# BCD_Source.net
KiCad netlist of a schematic drawn in EasyEDA Pro
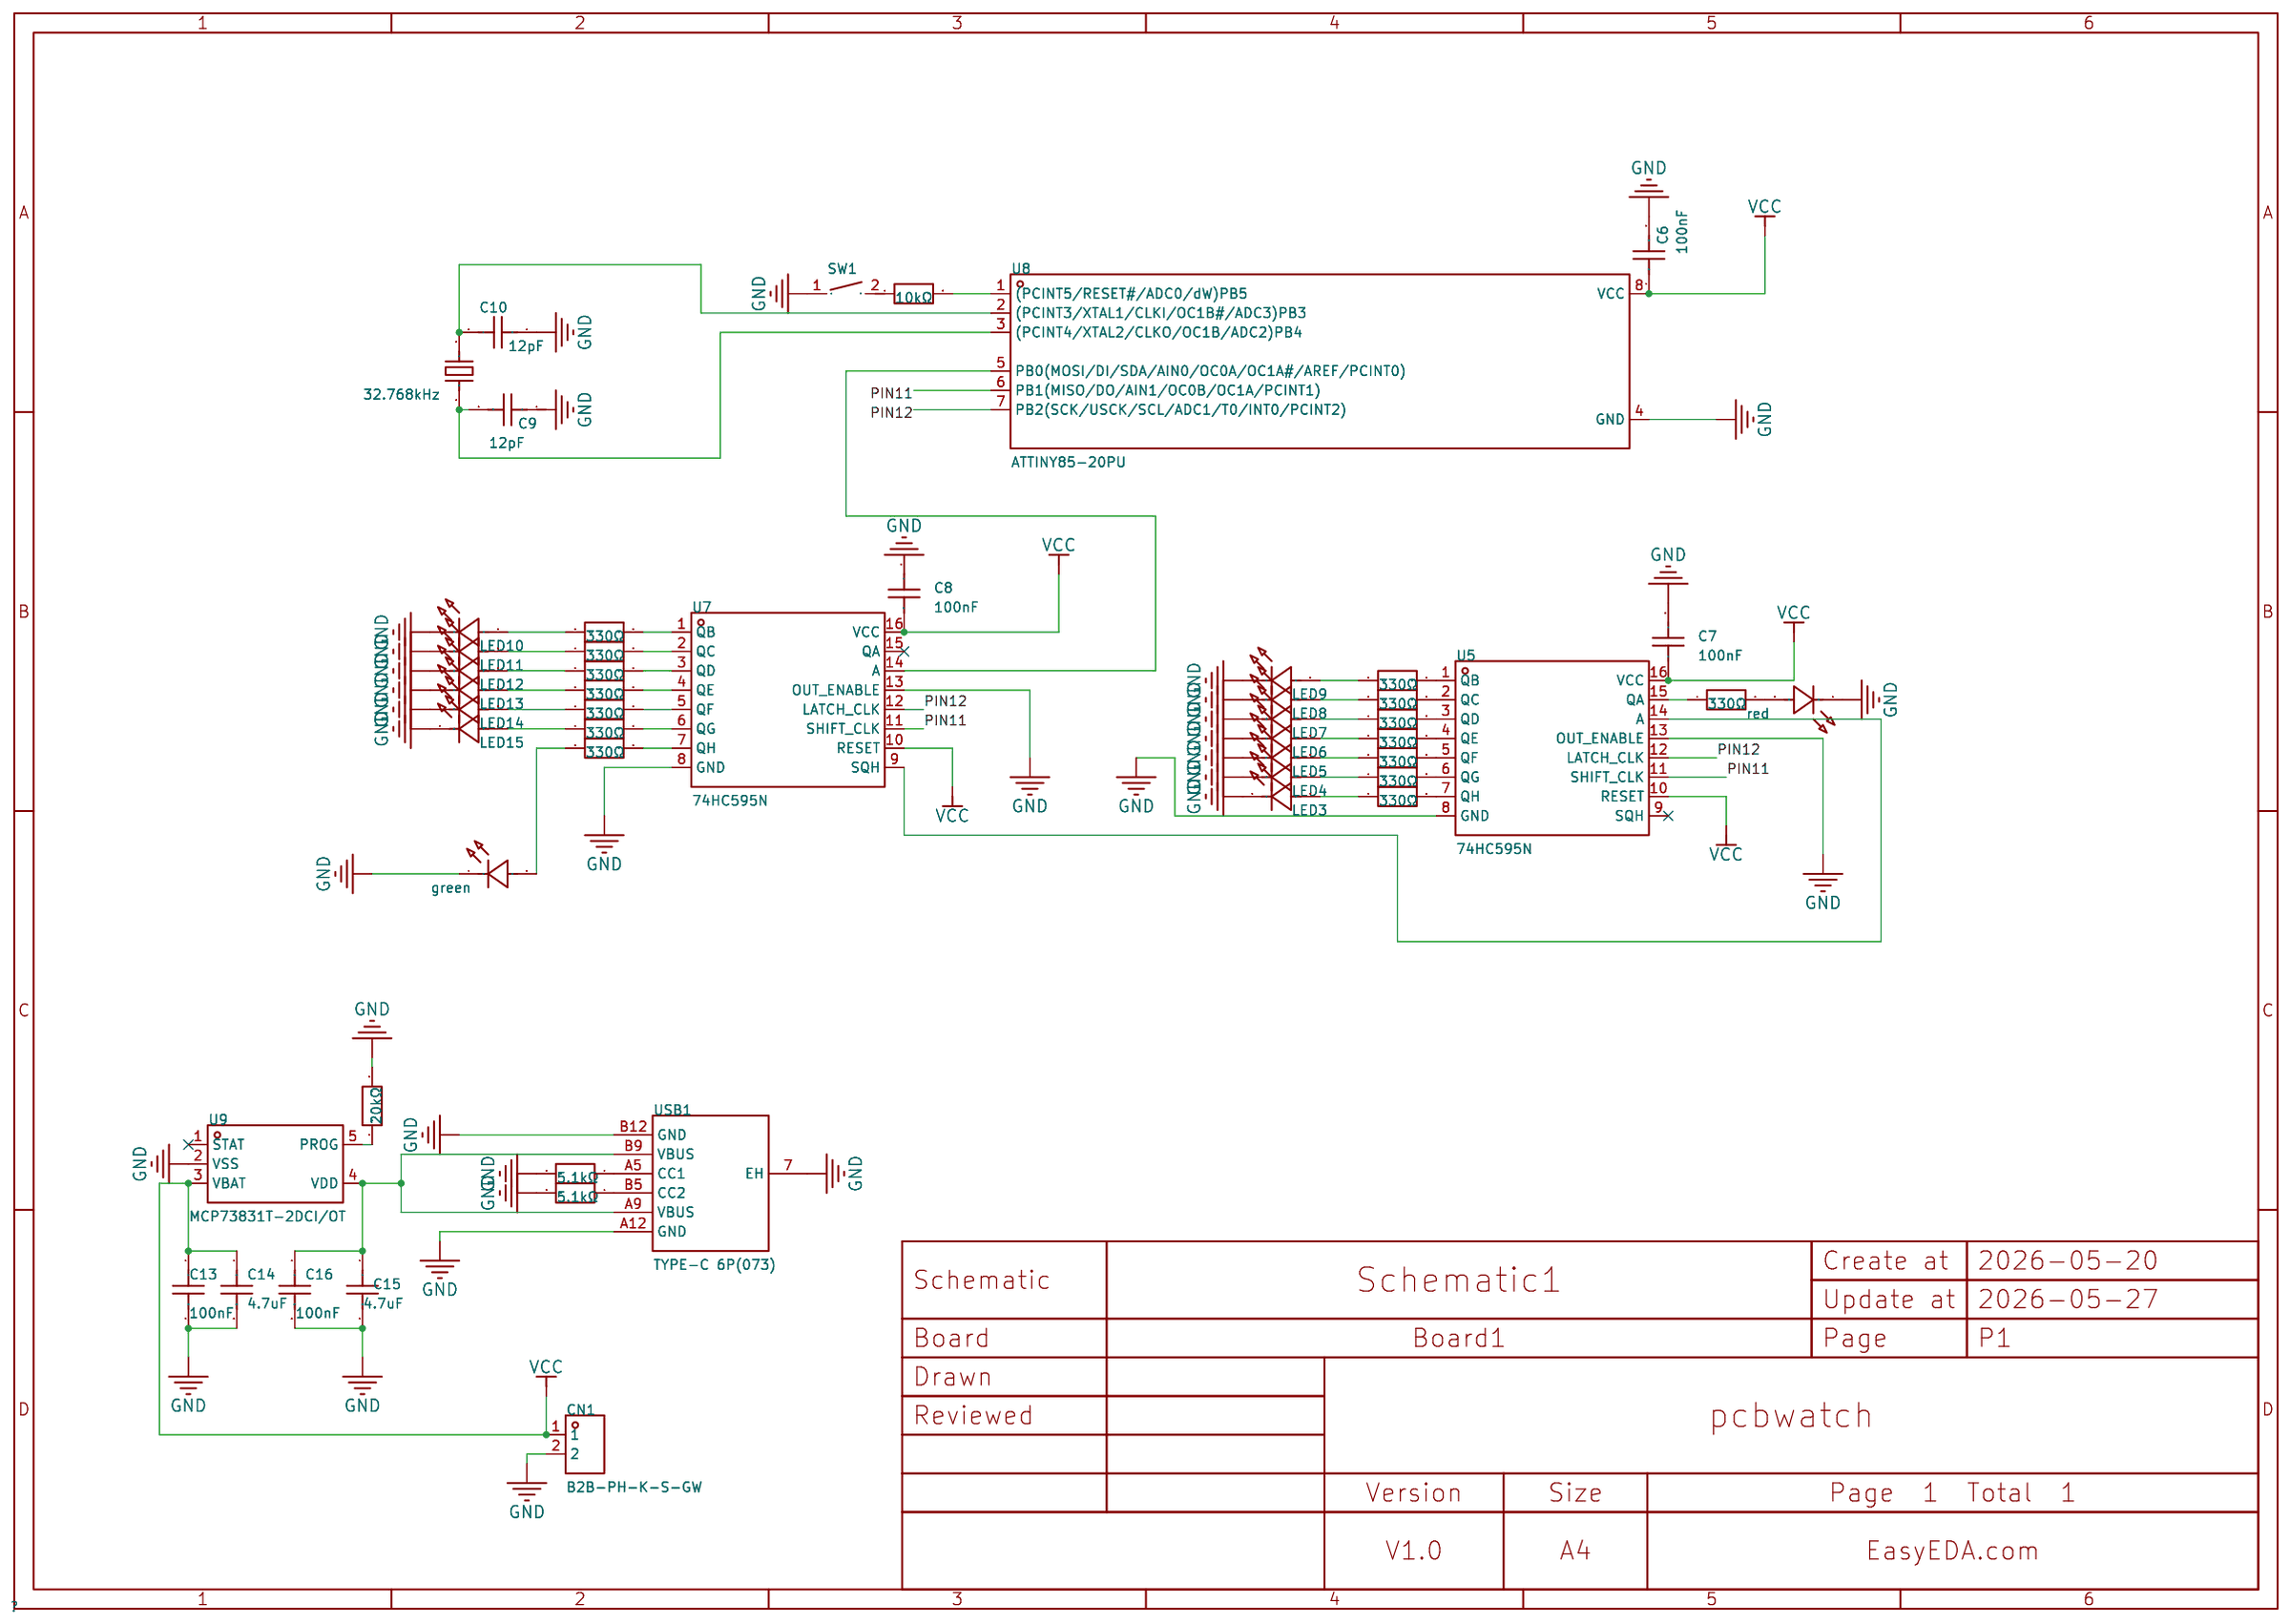
[diagram p0: schematic sheet]

(export (version "E")
  (design (tool "Eeschema 10.0.6"))
  (components
    (comp (ref "C6")
      (value "100nF")
      (footprint "easyedapro:CAP-TH_L5.8-W2.4-P2.54-D0.6")
      (fields
        (field (name "Manufacturer Part") "CC1H104ZA1ED3F5P1100")
        (field (name "Manufacturer") "Dersonic(德尔创)")
      )
      (libsource (lib "easyedapro") (part "CC1H104ZA1ED3F5P1100"))
    )
    (comp (ref "C7")
      (value "100nF")
      (footprint "easyedapro:CAP-TH_L5.8-W2.4-P2.54-D0.6")
      (fields
        (field (name "Manufacturer Part") "CC1H104ZA1ED3F5P1100")
        (field (name "Manufacturer") "Dersonic(德尔创)")
      )
      (libsource (lib "easyedapro") (part "CC1H104ZA1ED3F5P1100"))
    )
    (comp (ref "C8")
      (value "100nF")
      (footprint "easyedapro:CAP-TH_L5.8-W2.4-P2.54-D0.6")
      (fields
        (field (name "Manufacturer Part") "CC1H104ZA1ED3F5P1100")
        (field (name "Manufacturer") "Dersonic(德尔创)")
      )
      (libsource (lib "easyedapro") (part "CC1H104ZA1ED3F5P1100"))
    )
    (comp (ref "C9")
      (value "12pF")
      (footprint "easyedapro:CAP-TH_L5.8-W2.4-P2.54-D0.6")
      (fields
        (field (name "Manufacturer Part") "CC1H104ZA1ED3F5P1100")
        (field (name "Manufacturer") "Dersonic(德尔创)")
      )
      (libsource (lib "easyedapro") (part "CC1H104ZA1ED3F5P1100"))
    )
    (comp (ref "C10")
      (value "12pF")
      (footprint "easyedapro:CAP-TH_L5.8-W2.4-P2.54-D0.6")
      (fields
        (field (name "Manufacturer Part") "CC1H104ZA1ED3F5P1100")
        (field (name "Manufacturer") "Dersonic(德尔创)")
      )
      (libsource (lib "easyedapro") (part "CC1H104ZA1ED3F5P1100"))
    )
    (comp (ref "C13")
      (value "100nF")
      (footprint "easyedapro:CAP-TH_L5.8-W2.4-P2.54-D0.6")
      (fields
        (field (name "Manufacturer Part") "CC1H104ZA1ED3F5P1100")
        (field (name "Manufacturer") "Dersonic(德尔创)")
      )
      (libsource (lib "easyedapro") (part "CC1H104ZA1ED3F5P1100"))
    )
    (comp (ref "C14")
      (value "4.7uF")
      (footprint "easyedapro:CAP-TH_L5.8-W2.4-P2.54-D0.6")
      (fields
        (field (name "Manufacturer Part") "CC1H104ZA1ED3F5P1100")
        (field (name "Manufacturer") "Dersonic(德尔创)")
      )
      (libsource (lib "easyedapro") (part "CC1H104ZA1ED3F5P1100"))
    )
    (comp (ref "C15")
      (value "4.7uF")
      (footprint "easyedapro:CAP-TH_L5.8-W2.4-P2.54-D0.6")
      (fields
        (field (name "Manufacturer Part") "CC1H104ZA1ED3F5P1100")
        (field (name "Manufacturer") "Dersonic(德尔创)")
      )
      (libsource (lib "easyedapro") (part "CC1H104ZA1ED3F5P1100"))
    )
    (comp (ref "C16")
      (value "100nF")
      (footprint "easyedapro:CAP-TH_L5.8-W2.4-P2.54-D0.6")
      (fields
        (field (name "Manufacturer Part") "CC1H104ZA1ED3F5P1100")
        (field (name "Manufacturer") "Dersonic(德尔创)")
      )
      (libsource (lib "easyedapro") (part "CC1H104ZA1ED3F5P1100"))
    )
    (comp (ref "CN1")
      (value "B2B-PH-K-S-GW")
      (footprint "easyedapro:CONN-TH_B2B-PH-K-S")
      (fields (field (name "Manufacturer") "JST"))
      (libsource (lib "easyedapro") (part "B2B-PH-K-S-GW"))
    )
    (comp (ref "green")
      (value "TJ-S2012EX8T5ALC2R-A5")
      (footprint "easyedapro:LED0805-RD")
      (fields (field (name "Manufacturer") "TOGIALED(统佳)"))
      (libsource (lib "easyedapro") (part "TJ-S2012EX8T5ALC2R-A5"))
    )
    (comp (ref "LED3")
      (value "TJ-S2012EX8T5ALC2R-A5")
      (footprint "easyedapro:LED0805-RD")
      (fields (field (name "Manufacturer") "TOGIALED(统佳)"))
      (libsource (lib "easyedapro") (part "TJ-S2012EX8T5ALC2R-A5"))
    )
    (comp (ref "LED4")
      (value "TJ-S2012EX8T5ALC2R-A5")
      (footprint "easyedapro:LED0805-RD")
      (fields (field (name "Manufacturer") "TOGIALED(统佳)"))
      (libsource (lib "easyedapro") (part "TJ-S2012EX8T5ALC2R-A5"))
    )
    (comp (ref "LED5")
      (value "TJ-S2012EX8T5ALC2R-A5")
      (footprint "easyedapro:LED0805-RD")
      (fields (field (name "Manufacturer") "TOGIALED(统佳)"))
      (libsource (lib "easyedapro") (part "TJ-S2012EX8T5ALC2R-A5"))
    )
    (comp (ref "LED6")
      (value "TJ-S2012EX8T5ALC2R-A5")
      (footprint "easyedapro:LED0805-RD")
      (fields (field (name "Manufacturer") "TOGIALED(统佳)"))
      (libsource (lib "easyedapro") (part "TJ-S2012EX8T5ALC2R-A5"))
    )
    (comp (ref "LED7")
      (value "TJ-S2012EX8T5ALC2R-A5")
      (footprint "easyedapro:LED0805-RD")
      (fields (field (name "Manufacturer") "TOGIALED(统佳)"))
      (libsource (lib "easyedapro") (part "TJ-S2012EX8T5ALC2R-A5"))
    )
    (comp (ref "LED8")
      (value "TJ-S2012EX8T5ALC2R-A5")
      (footprint "easyedapro:LED0805-RD")
      (fields (field (name "Manufacturer") "TOGIALED(统佳)"))
      (libsource (lib "easyedapro") (part "TJ-S2012EX8T5ALC2R-A5"))
    )
    (comp (ref "LED9")
      (value "TJ-S2012EX8T5ALC2R-A5")
      (footprint "easyedapro:LED0805-RD")
      (fields (field (name "Manufacturer") "TOGIALED(统佳)"))
      (libsource (lib "easyedapro") (part "TJ-S2012EX8T5ALC2R-A5"))
    )
    (comp (ref "LED10")
      (value "TJ-S2012EX8T5ALC2R-A5")
      (footprint "easyedapro:LED0805-RD")
      (fields (field (name "Manufacturer") "TOGIALED(统佳)"))
      (libsource (lib "easyedapro") (part "TJ-S2012EX8T5ALC2R-A5"))
    )
    (comp (ref "LED11")
      (value "TJ-S2012EX8T5ALC2R-A5")
      (footprint "easyedapro:LED0805-RD")
      (fields (field (name "Manufacturer") "TOGIALED(统佳)"))
      (libsource (lib "easyedapro") (part "TJ-S2012EX8T5ALC2R-A5"))
    )
    (comp (ref "LED12")
      (value "TJ-S2012EX8T5ALC2R-A5")
      (footprint "easyedapro:LED0805-RD")
      (fields (field (name "Manufacturer") "TOGIALED(统佳)"))
      (libsource (lib "easyedapro") (part "TJ-S2012EX8T5ALC2R-A5"))
    )
    (comp (ref "LED13")
      (value "TJ-S2012EX8T5ALC2R-A5")
      (footprint "easyedapro:LED0805-RD")
      (fields (field (name "Manufacturer") "TOGIALED(统佳)"))
      (libsource (lib "easyedapro") (part "TJ-S2012EX8T5ALC2R-A5"))
    )
    (comp (ref "LED14")
      (value "TJ-S2012EX8T5ALC2R-A5")
      (footprint "easyedapro:LED0805-RD")
      (fields (field (name "Manufacturer") "TOGIALED(统佳)"))
      (libsource (lib "easyedapro") (part "TJ-S2012EX8T5ALC2R-A5"))
    )
    (comp (ref "LED15")
      (value "TJ-S2012EX8T5ALC2R-A5")
      (footprint "easyedapro:LED0805-RD")
      (fields (field (name "Manufacturer") "TOGIALED(统佳)"))
      (libsource (lib "easyedapro") (part "TJ-S2012EX8T5ALC2R-A5"))
    )
    (comp (ref "R20")
      (value "330Ω")
      (footprint "easyedapro:RES-TH_BD2.3-L6.5-P10.50-D0.5")
      (fields (field (name "Manufacturer Part") "MF1/4W-1KΩ±1%T52") (field (name "Manufacturer") "华星机电"))
      (libsource (lib "easyedapro") (part "MF1/4W-1KΩ±1%T52"))
    )
    (comp (ref "R21")
      (value "330Ω")
      (footprint "easyedapro:RES-TH_BD2.3-L6.5-P10.50-D0.5")
      (fields (field (name "Manufacturer Part") "MF1/4W-1KΩ±1%T52") (field (name "Manufacturer") "华星机电"))
      (libsource (lib "easyedapro") (part "MF1/4W-1KΩ±1%T52"))
    )
    (comp (ref "R22")
      (value "330Ω")
      (footprint "easyedapro:RES-TH_BD2.3-L6.5-P10.50-D0.5")
      (fields (field (name "Manufacturer Part") "MF1/4W-1KΩ±1%T52") (field (name "Manufacturer") "华星机电"))
      (libsource (lib "easyedapro") (part "MF1/4W-1KΩ±1%T52"))
    )
    (comp (ref "R23")
      (value "330Ω")
      (footprint "easyedapro:RES-TH_BD2.3-L6.5-P10.50-D0.5")
      (fields (field (name "Manufacturer Part") "MF1/4W-1KΩ±1%T52") (field (name "Manufacturer") "华星机电"))
      (libsource (lib "easyedapro") (part "MF1/4W-1KΩ±1%T52"))
    )
    (comp (ref "R24")
      (value "330Ω")
      (footprint "easyedapro:RES-TH_BD2.3-L6.5-P10.50-D0.5")
      (fields (field (name "Manufacturer Part") "MF1/4W-1KΩ±1%T52") (field (name "Manufacturer") "华星机电"))
      (libsource (lib "easyedapro") (part "MF1/4W-1KΩ±1%T52"))
    )
    (comp (ref "R25")
      (value "330Ω")
      (footprint "easyedapro:RES-TH_BD2.3-L6.5-P10.50-D0.5")
      (fields (field (name "Manufacturer Part") "MF1/4W-1KΩ±1%T52") (field (name "Manufacturer") "华星机电"))
      (libsource (lib "easyedapro") (part "MF1/4W-1KΩ±1%T52"))
    )
    (comp (ref "R26")
      (value "330Ω")
      (footprint "easyedapro:RES-TH_BD2.3-L6.5-P10.50-D0.5")
      (fields (field (name "Manufacturer Part") "MF1/4W-1KΩ±1%T52") (field (name "Manufacturer") "华星机电"))
      (libsource (lib "easyedapro") (part "MF1/4W-1KΩ±1%T52"))
    )
    (comp (ref "R27")
      (value "330Ω")
      (footprint "easyedapro:RES-TH_BD2.3-L6.5-P10.50-D0.5")
      (fields (field (name "Manufacturer Part") "MF1/4W-1KΩ±1%T52") (field (name "Manufacturer") "华星机电"))
      (libsource (lib "easyedapro") (part "MF1/4W-1KΩ±1%T52"))
    )
    (comp (ref "R28")
      (value "330Ω")
      (footprint "easyedapro:RES-TH_BD2.3-L6.5-P10.50-D0.5")
      (fields (field (name "Manufacturer Part") "MF1/4W-1KΩ±1%T52") (field (name "Manufacturer") "华星机电"))
      (libsource (lib "easyedapro") (part "MF1/4W-1KΩ±1%T52"))
    )
    (comp (ref "R29")
      (value "330Ω")
      (footprint "easyedapro:RES-TH_BD2.3-L6.5-P10.50-D0.5")
      (fields (field (name "Manufacturer Part") "MF1/4W-1KΩ±1%T52") (field (name "Manufacturer") "华星机电"))
      (libsource (lib "easyedapro") (part "MF1/4W-1KΩ±1%T52"))
    )
    (comp (ref "R30")
      (value "330Ω")
      (footprint "easyedapro:RES-TH_BD2.3-L6.5-P10.50-D0.5")
      (fields (field (name "Manufacturer Part") "MF1/4W-1KΩ±1%T52") (field (name "Manufacturer") "华星机电"))
      (libsource (lib "easyedapro") (part "MF1/4W-1KΩ±1%T52"))
    )
    (comp (ref "R31")
      (value "330Ω")
      (footprint "easyedapro:RES-TH_BD2.3-L6.5-P10.50-D0.5")
      (fields (field (name "Manufacturer Part") "MF1/4W-1KΩ±1%T52") (field (name "Manufacturer") "华星机电"))
      (libsource (lib "easyedapro") (part "MF1/4W-1KΩ±1%T52"))
    )
    (comp (ref "R32")
      (value "330Ω")
      (footprint "easyedapro:RES-TH_BD2.3-L6.5-P10.50-D0.5")
      (fields (field (name "Manufacturer Part") "MF1/4W-1KΩ±1%T52") (field (name "Manufacturer") "华星机电"))
      (libsource (lib "easyedapro") (part "MF1/4W-1KΩ±1%T52"))
    )
    (comp (ref "R33")
      (value "330Ω")
      (footprint "easyedapro:RES-TH_BD2.3-L6.5-P10.50-D0.5")
      (fields (field (name "Manufacturer Part") "MF1/4W-1KΩ±1%T52") (field (name "Manufacturer") "华星机电"))
      (libsource (lib "easyedapro") (part "MF1/4W-1KΩ±1%T52"))
    )
    (comp (ref "R34")
      (value "330Ω")
      (footprint "easyedapro:RES-TH_BD2.3-L6.5-P10.50-D0.5")
      (fields (field (name "Manufacturer Part") "MF1/4W-1KΩ±1%T52") (field (name "Manufacturer") "华星机电"))
      (libsource (lib "easyedapro") (part "MF1/4W-1KΩ±1%T52"))
    )
    (comp (ref "R36")
      (value "10kΩ")
      (footprint "easyedapro:RES-TH_BD2.3-L6.5-P10.50-D0.5")
      (fields (field (name "Manufacturer Part") "MF1/4W-1KΩ±1%T52") (field (name "Manufacturer") "华星机电"))
      (libsource (lib "easyedapro") (part "MF1/4W-1KΩ±1%T52"))
    )
    (comp (ref "R40")
      (value "20kΩ")
      (footprint "easyedapro:RES-TH_BD2.3-L6.5-P10.50-D0.5")
      (fields (field (name "Manufacturer Part") "MF1/4W-1KΩ±1%T52") (field (name "Manufacturer") "华星机电"))
      (libsource (lib "easyedapro") (part "MF1/4W-1KΩ±1%T52"))
    )
    (comp (ref "R41")
      (value "5.1kΩ")
      (footprint "easyedapro:RES-TH_BD2.3-L6.5-P10.50-D0.5")
      (fields (field (name "Manufacturer Part") "MF1/4W-1KΩ±1%T52") (field (name "Manufacturer") "华星机电"))
      (libsource (lib "easyedapro") (part "MF1/4W-1KΩ±1%T52"))
    )
    (comp (ref "R42")
      (value "5.1kΩ")
      (footprint "easyedapro:RES-TH_BD2.3-L6.5-P10.50-D0.5")
      (fields (field (name "Manufacturer Part") "MF1/4W-1KΩ±1%T52") (field (name "Manufacturer") "华星机电"))
      (libsource (lib "easyedapro") (part "MF1/4W-1KΩ±1%T52"))
    )
    (comp (ref "red")
      (value "TJ-S2012EX8T5ALC2R-A5")
      (footprint "easyedapro:LED0805-RD")
      (fields (field (name "Manufacturer") "TOGIALED(统佳)"))
      (libsource (lib "easyedapro") (part "TJ-S2012EX8T5ALC2R-A5"))
    )
    (comp (ref "SW1")
      (value "HX 3x4x2-2P-1.6N TACTILE SWITCH")
      (footprint "easyedapro:KEY-SMD_L4.0-W3.0-LS4.9-1")
      (fields (field (name "Manufacturer") "hanxia(韩下)"))
      (libsource (lib "easyedapro") (part "HX 3X4X2-2P-1.6N TACTILE SWITCH"))
    )
    (comp (ref "U5")
      (value "74HC595N")
      (footprint "easyedapro:DIP-16_L19.8-W6.5-P2.54-LS7.6-BL")
      (fields (field (name "Manufacturer") "HTC"))
      (libsource (lib "easyedapro") (part "74HC595N_C669328"))
    )
    (comp (ref "U7")
      (value "74HC595N")
      (footprint "easyedapro:DIP-16_L19.8-W6.5-P2.54-LS7.6-BL")
      (fields (field (name "Manufacturer") "HTC"))
      (libsource (lib "easyedapro") (part "74HC595N_C669328"))
    )
    (comp (ref "U8")
      (value "ATTINY85-20PU")
      (footprint "easyedapro:PDIP-8_L9.3-W6.4-P2.54-LS7.9-BL-1")
      (fields (field (name "Manufacturer") "MICROCHIP(美国微芯)"))
      (libsource (lib "easyedapro") (part "ATTINY85-20PU"))
    )
    (comp (ref "U9")
      (value "MCP73831T-2DCI/OT")
      (footprint "easyedapro:SOT-23-5_L2.9-W1.6-P0.95-LS2.8-BL")
      (fields (field (name "Manufacturer") "MICROCHIP(美国微芯)"))
      (libsource (lib "easyedapro") (part "MCP73831T-2DCI/OT"))
    )
    (comp (ref "USB1")
      (value "TYPE-C 6P(073)")
      (footprint "easyedapro:TYPE-C-SMD_TYPE-C-6P-073")
      (fields (field (name "Manufacturer") "SHOU HAN(首韩)"))
      (libsource (lib "easyedapro") (part "TYPE-C 6P(073)"))
    )
    (comp (ref "X1")
      (value "32.768kHz")
      (footprint "easyedapro:OSC-TH_BD2.0-P0.70-D0.3")
      (fields
        (field (name "Manufacturer Part") "TAXD32768K2BGBBZT2S")
        (field (name "Manufacturer") "YJX(雅晶鑫)")
      )
      (libsource (lib "easyedapro") (part "TAXD32768K2BGBBZT2S"))
    )
  )
  (nets
    (net (code "1") (name "/PIN11") (class "Default")
      (node (ref "U5") (pin "11") (pinfunction "SHIFT_CLK_11") (pintype "unspecified"))
      (node (ref "U7") (pin "11") (pinfunction "SHIFT_CLK_11") (pintype "unspecified"))
      (node (ref "U8") (pin "6") (pinfunction "PB1(MISO/DO/AIN1/OC0B/OC1A/PCINT1)_6") (pintype "unspecified"))
    )
    (net (code "2") (name "/PIN12") (class "Default")
      (node (ref "U5") (pin "12") (pinfunction "LATCH_CLK_12") (pintype "unspecified"))
      (node (ref "U7") (pin "12") (pinfunction "LATCH_CLK_12") (pintype "unspecified"))
      (node (ref "U8") (pin "7") (pinfunction "PB2(SCK/USCK/SCL/ADC1/T0/INT0/PCINT2)_7") (pintype "unspecified"))
    )
    (net (code "3") (name "GND") (class "Default")
      (node (ref "C10") (pin "1") (pinfunction "1_1") (pintype "unspecified"))
      (node (ref "C13") (pin "2") (pinfunction "2_2") (pintype "unspecified"))
      (node (ref "C14") (pin "2") (pinfunction "2_2") (pintype "unspecified"))
      (node (ref "C15") (pin "2") (pinfunction "2_2") (pintype "unspecified"))
      (node (ref "C16") (pin "2") (pinfunction "2_2") (pintype "unspecified"))
      (node (ref "C6") (pin "2") (pinfunction "2_2") (pintype "unspecified"))
      (node (ref "C7") (pin "2") (pinfunction "2_2") (pintype "unspecified"))
      (node (ref "C8") (pin "1") (pinfunction "1_1") (pintype "unspecified"))
      (node (ref "C9") (pin "1") (pinfunction "1_1") (pintype "unspecified"))
      (node (ref "CN1") (pin "2") (pinfunction "2_2") (pintype "unspecified"))
      (node (ref "LED10") (pin "1") (pinfunction "C_1") (pintype "unspecified"))
      (node (ref "LED11") (pin "1") (pinfunction "C_1") (pintype "unspecified"))
      (node (ref "LED12") (pin "1") (pinfunction "C_1") (pintype "unspecified"))
      (node (ref "LED13") (pin "1") (pinfunction "C_1") (pintype "unspecified"))
      (node (ref "LED14") (pin "1") (pinfunction "C_1") (pintype "unspecified"))
      (node (ref "LED15") (pin "1") (pinfunction "C_1") (pintype "unspecified"))
      (node (ref "LED3") (pin "1") (pinfunction "C_1") (pintype "unspecified"))
      (node (ref "LED4") (pin "1") (pinfunction "C_1") (pintype "unspecified"))
      (node (ref "LED5") (pin "1") (pinfunction "C_1") (pintype "unspecified"))
      (node (ref "LED6") (pin "1") (pinfunction "C_1") (pintype "unspecified"))
      (node (ref "LED7") (pin "1") (pinfunction "C_1") (pintype "unspecified"))
      (node (ref "LED8") (pin "1") (pinfunction "C_1") (pintype "unspecified"))
      (node (ref "LED9") (pin "1") (pinfunction "C_1") (pintype "unspecified"))
      (node (ref "R40") (pin "2") (pinfunction "2_2") (pintype "unspecified"))
      (node (ref "R41") (pin "2") (pinfunction "2_2") (pintype "unspecified"))
      (node (ref "R42") (pin "2") (pinfunction "2_2") (pintype "unspecified"))
      (node (ref "SW1") (pin "1") (pinfunction "1_1") (pintype "unspecified"))
      (node (ref "U5") (pin "13") (pinfunction "OUT_ENABLE_13") (pintype "unspecified"))
      (node (ref "U5") (pin "8") (pinfunction "GND_8") (pintype "unspecified"))
      (node (ref "U7") (pin "13") (pinfunction "OUT_ENABLE_13") (pintype "unspecified"))
      (node (ref "U7") (pin "8") (pinfunction "GND_8") (pintype "unspecified"))
      (node (ref "U8") (pin "4") (pinfunction "GND_4") (pintype "unspecified"))
      (node (ref "U9") (pin "2") (pinfunction "VSS_2") (pintype "unspecified"))
      (node (ref "USB1") (pin "7") (pinfunction "EH_7") (pintype "unspecified"))
      (node (ref "USB1") (pin "A12") (pinfunction "GND_A12") (pintype "unspecified"))
      (node (ref "USB1") (pin "B12") (pinfunction "GND_B12") (pintype "unspecified"))
      (node (ref "green") (pin "1") (pinfunction "C_1") (pintype "unspecified"))
      (node (ref "red") (pin "1") (pinfunction "C_1") (pintype "unspecified"))
    )
    (net (code "4") (name "Net-(LED3-A)") (class "Default")
      (node (ref "LED3") (pin "2") (pinfunction "A_2") (pintype "unspecified"))
      (node (ref "R33") (pin "1") (pinfunction "1_1") (pintype "unspecified"))
    )
    (net (code "5") (name "Net-(LED4-A)") (class "Default")
      (node (ref "LED4") (pin "2") (pinfunction "A_2") (pintype "unspecified"))
      (node (ref "R32") (pin "1") (pinfunction "1_1") (pintype "unspecified"))
    )
    (net (code "6") (name "Net-(LED5-A)") (class "Default")
      (node (ref "LED5") (pin "2") (pinfunction "A_2") (pintype "unspecified"))
      (node (ref "R31") (pin "1") (pinfunction "1_1") (pintype "unspecified"))
    )
    (net (code "7") (name "Net-(LED6-A)") (class "Default")
      (node (ref "LED6") (pin "2") (pinfunction "A_2") (pintype "unspecified"))
      (node (ref "R30") (pin "1") (pinfunction "1_1") (pintype "unspecified"))
    )
    (net (code "8") (name "Net-(LED7-A)") (class "Default")
      (node (ref "LED7") (pin "2") (pinfunction "A_2") (pintype "unspecified"))
      (node (ref "R29") (pin "1") (pinfunction "1_1") (pintype "unspecified"))
    )
    (net (code "9") (name "Net-(LED8-A)") (class "Default")
      (node (ref "LED8") (pin "2") (pinfunction "A_2") (pintype "unspecified"))
      (node (ref "R28") (pin "1") (pinfunction "1_1") (pintype "unspecified"))
    )
    (net (code "10") (name "Net-(LED9-A)") (class "Default")
      (node (ref "LED9") (pin "2") (pinfunction "A_2") (pintype "unspecified"))
      (node (ref "R27") (pin "1") (pinfunction "1_1") (pintype "unspecified"))
    )
    (net (code "11") (name "Net-(LED10-A)") (class "Default")
      (node (ref "LED10") (pin "2") (pinfunction "A_2") (pintype "unspecified"))
      (node (ref "R20") (pin "1") (pinfunction "1_1") (pintype "unspecified"))
    )
    (net (code "12") (name "Net-(LED11-A)") (class "Default")
      (node (ref "LED11") (pin "2") (pinfunction "A_2") (pintype "unspecified"))
      (node (ref "R21") (pin "1") (pinfunction "1_1") (pintype "unspecified"))
    )
    (net (code "13") (name "Net-(LED12-A)") (class "Default")
      (node (ref "LED12") (pin "2") (pinfunction "A_2") (pintype "unspecified"))
      (node (ref "R22") (pin "1") (pinfunction "1_1") (pintype "unspecified"))
    )
    (net (code "14") (name "Net-(LED13-A)") (class "Default")
      (node (ref "LED13") (pin "2") (pinfunction "A_2") (pintype "unspecified"))
      (node (ref "R23") (pin "1") (pinfunction "1_1") (pintype "unspecified"))
    )
    (net (code "15") (name "Net-(LED14-A)") (class "Default")
      (node (ref "LED14") (pin "2") (pinfunction "A_2") (pintype "unspecified"))
      (node (ref "R24") (pin "1") (pinfunction "1_1") (pintype "unspecified"))
    )
    (net (code "16") (name "Net-(LED15-A)") (class "Default")
      (node (ref "LED15") (pin "2") (pinfunction "A_2") (pintype "unspecified"))
      (node (ref "R25") (pin "1") (pinfunction "1_1") (pintype "unspecified"))
    )
    (net (code "17") (name "Net-(R36-Pad1)") (class "Default")
      (node (ref "R36") (pin "1") (pinfunction "1_1") (pintype "unspecified"))
      (node (ref "SW1") (pin "2") (pinfunction "2_2") (pintype "unspecified"))
    )
    (net (code "18") (name "Net-(U5-A)") (class "Default")
      (node (ref "U5") (pin "14") (pinfunction "A_14") (pintype "unspecified"))
      (node (ref "U7") (pin "9") (pinfunction "SQH_9") (pintype "unspecified"))
    )
    (net (code "19") (name "Net-(U5-QA)") (class "Default")
      (node (ref "R34") (pin "1") (pinfunction "1_1") (pintype "unspecified"))
      (node (ref "U5") (pin "15") (pinfunction "QA_15") (pintype "unspecified"))
    )
    (net (code "20") (name "Net-(U5-QB)") (class "Default")
      (node (ref "R27") (pin "2") (pinfunction "2_2") (pintype "unspecified"))
      (node (ref "U5") (pin "1") (pinfunction "QB_1") (pintype "unspecified"))
    )
    (net (code "21") (name "Net-(U5-QC)") (class "Default")
      (node (ref "R28") (pin "2") (pinfunction "2_2") (pintype "unspecified"))
      (node (ref "U5") (pin "2") (pinfunction "QC_2") (pintype "unspecified"))
    )
    (net (code "22") (name "Net-(U5-QD)") (class "Default")
      (node (ref "R29") (pin "2") (pinfunction "2_2") (pintype "unspecified"))
      (node (ref "U5") (pin "3") (pinfunction "QD_3") (pintype "unspecified"))
    )
    (net (code "23") (name "Net-(U5-QE)") (class "Default")
      (node (ref "R30") (pin "2") (pinfunction "2_2") (pintype "unspecified"))
      (node (ref "U5") (pin "4") (pinfunction "QE_4") (pintype "unspecified"))
    )
    (net (code "24") (name "Net-(U5-QF)") (class "Default")
      (node (ref "R31") (pin "2") (pinfunction "2_2") (pintype "unspecified"))
      (node (ref "U5") (pin "5") (pinfunction "QF_5") (pintype "unspecified"))
    )
    (net (code "25") (name "Net-(U5-QG)") (class "Default")
      (node (ref "R32") (pin "2") (pinfunction "2_2") (pintype "unspecified"))
      (node (ref "U5") (pin "6") (pinfunction "QG_6") (pintype "unspecified"))
    )
    (net (code "26") (name "Net-(U5-QH)") (class "Default")
      (node (ref "R33") (pin "2") (pinfunction "2_2") (pintype "unspecified"))
      (node (ref "U5") (pin "7") (pinfunction "QH_7") (pintype "unspecified"))
    )
    (net (code "27") (name "Net-(U7-A)") (class "Default")
      (node (ref "U7") (pin "14") (pinfunction "A_14") (pintype "unspecified"))
      (node (ref "U8") (pin "5") (pinfunction "PB0(MOSI/DI/SDA/AIN0/OC0A/OC1A#/AREF/PCINT0)_5") (pintype "unspecified"))
    )
    (net (code "28") (name "Net-(U7-QB)") (class "Default")
      (node (ref "R20") (pin "2") (pinfunction "2_2") (pintype "unspecified"))
      (node (ref "U7") (pin "1") (pinfunction "QB_1") (pintype "unspecified"))
    )
    (net (code "29") (name "Net-(U7-QC)") (class "Default")
      (node (ref "R21") (pin "2") (pinfunction "2_2") (pintype "unspecified"))
      (node (ref "U7") (pin "2") (pinfunction "QC_2") (pintype "unspecified"))
    )
    (net (code "30") (name "Net-(U7-QD)") (class "Default")
      (node (ref "R22") (pin "2") (pinfunction "2_2") (pintype "unspecified"))
      (node (ref "U7") (pin "3") (pinfunction "QD_3") (pintype "unspecified"))
    )
    (net (code "31") (name "Net-(U7-QE)") (class "Default")
      (node (ref "R23") (pin "2") (pinfunction "2_2") (pintype "unspecified"))
      (node (ref "U7") (pin "4") (pinfunction "QE_4") (pintype "unspecified"))
    )
    (net (code "32") (name "Net-(U7-QF)") (class "Default")
      (node (ref "R24") (pin "2") (pinfunction "2_2") (pintype "unspecified"))
      (node (ref "U7") (pin "5") (pinfunction "QF_5") (pintype "unspecified"))
    )
    (net (code "33") (name "Net-(U7-QG)") (class "Default")
      (node (ref "R25") (pin "2") (pinfunction "2_2") (pintype "unspecified"))
      (node (ref "U7") (pin "6") (pinfunction "QG_6") (pintype "unspecified"))
    )
    (net (code "34") (name "Net-(U7-QH)") (class "Default")
      (node (ref "R26") (pin "2") (pinfunction "2_2") (pintype "unspecified"))
      (node (ref "U7") (pin "7") (pinfunction "QH_7") (pintype "unspecified"))
    )
    (net (code "35") (name "Net-(U8-(PCINT3{slash}XTAL1{slash}CLKI{slash}OC1B#{slash}ADC3)PB3)") (class "Default")
      (node (ref "C10") (pin "2") (pinfunction "2_2") (pintype "unspecified"))
      (node (ref "U8") (pin "2") (pinfunction "(PCINT3/XTAL1/CLKI/OC1B#/ADC3)PB3_2") (pintype "unspecified"))
      (node (ref "X1") (pin "2") (pinfunction "2_2") (pintype "input"))
    )
    (net (code "36") (name "Net-(U8-(PCINT4{slash}XTAL2{slash}CLKO{slash}OC1B{slash}ADC2)PB4)") (class "Default")
      (node (ref "C9") (pin "2") (pinfunction "2_2") (pintype "unspecified"))
      (node (ref "U8") (pin "3") (pinfunction "(PCINT4/XTAL2/CLKO/OC1B/ADC2)PB4_3") (pintype "unspecified"))
      (node (ref "X1") (pin "1") (pinfunction "1_1") (pintype "input"))
    )
    (net (code "37") (name "Net-(U8-(PCINT5{slash}RESET#{slash}ADC0{slash}dW)PB5)") (class "Default")
      (node (ref "R36") (pin "2") (pinfunction "2_2") (pintype "unspecified"))
      (node (ref "U8") (pin "1") (pinfunction "(PCINT5/RESET#/ADC0/dW)PB5_1") (pintype "unspecified"))
    )
    (net (code "38") (name "Net-(U9-PROG)") (class "Default")
      (node (ref "R40") (pin "1") (pinfunction "1_1") (pintype "unspecified"))
      (node (ref "U9") (pin "5") (pinfunction "PROG_5") (pintype "unspecified"))
    )
    (net (code "39") (name "Net-(U9-VDD)") (class "Default")
      (node (ref "C15") (pin "1") (pinfunction "1_1") (pintype "unspecified"))
      (node (ref "C16") (pin "1") (pinfunction "1_1") (pintype "unspecified"))
      (node (ref "U9") (pin "4") (pinfunction "VDD_4") (pintype "unspecified"))
      (node (ref "USB1") (pin "A9") (pinfunction "VBUS_A9") (pintype "unspecified"))
      (node (ref "USB1") (pin "B9") (pinfunction "VBUS_B9") (pintype "unspecified"))
    )
    (net (code "40") (name "Net-(USB1-CC1)") (class "Default")
      (node (ref "R41") (pin "1") (pinfunction "1_1") (pintype "unspecified"))
      (node (ref "USB1") (pin "A5") (pinfunction "CC1_A5") (pintype "unspecified"))
    )
    (net (code "41") (name "Net-(USB1-CC2)") (class "Default")
      (node (ref "R42") (pin "1") (pinfunction "1_1") (pintype "unspecified"))
      (node (ref "USB1") (pin "B5") (pinfunction "CC2_B5") (pintype "unspecified"))
    )
    (net (code "42") (name "Net-(green-A)") (class "Default")
      (node (ref "R26") (pin "1") (pinfunction "1_1") (pintype "unspecified"))
      (node (ref "green") (pin "2") (pinfunction "A_2") (pintype "unspecified"))
    )
    (net (code "43") (name "Net-(red-A)") (class "Default")
      (node (ref "R34") (pin "2") (pinfunction "2_2") (pintype "unspecified"))
      (node (ref "red") (pin "2") (pinfunction "A_2") (pintype "unspecified"))
    )
    (net (code "44") (name "VCC") (class "Default")
      (node (ref "C13") (pin "1") (pinfunction "1_1") (pintype "unspecified"))
      (node (ref "C14") (pin "1") (pinfunction "1_1") (pintype "unspecified"))
      (node (ref "C6") (pin "1") (pinfunction "1_1") (pintype "unspecified"))
      (node (ref "C7") (pin "1") (pinfunction "1_1") (pintype "unspecified"))
      (node (ref "C8") (pin "2") (pinfunction "2_2") (pintype "unspecified"))
      (node (ref "CN1") (pin "1") (pinfunction "1_1") (pintype "unspecified"))
      (node (ref "U5") (pin "10") (pinfunction "RESET_10") (pintype "unspecified"))
      (node (ref "U5") (pin "16") (pinfunction "VCC_16") (pintype "unspecified"))
      (node (ref "U7") (pin "10") (pinfunction "RESET_10") (pintype "unspecified"))
      (node (ref "U7") (pin "16") (pinfunction "VCC_16") (pintype "unspecified"))
      (node (ref "U8") (pin "8") (pinfunction "VCC_8") (pintype "unspecified"))
      (node (ref "U9") (pin "3") (pinfunction "VBAT_3") (pintype "unspecified"))
    )
    (net (code "45") (name "unconnected-(U5-SQH-Pad9)") (class "Default")
      (node (ref "U5") (pin "9") (pinfunction "SQH_9") (pintype "unspecified+no_connect"))
    )
    (net (code "46") (name "unconnected-(U7-QA-Pad15)") (class "Default")
      (node (ref "U7") (pin "15") (pinfunction "QA_15") (pintype "unspecified+no_connect"))
    )
    (net (code "47") (name "unconnected-(U9-STAT-Pad1)") (class "Default")
      (node (ref "U9") (pin "1") (pinfunction "STAT_1") (pintype "unspecified+no_connect"))
    )
  )
)
